# Differential_Opamp.net
KiCad netlist of a schematic drawn in Altium Designer
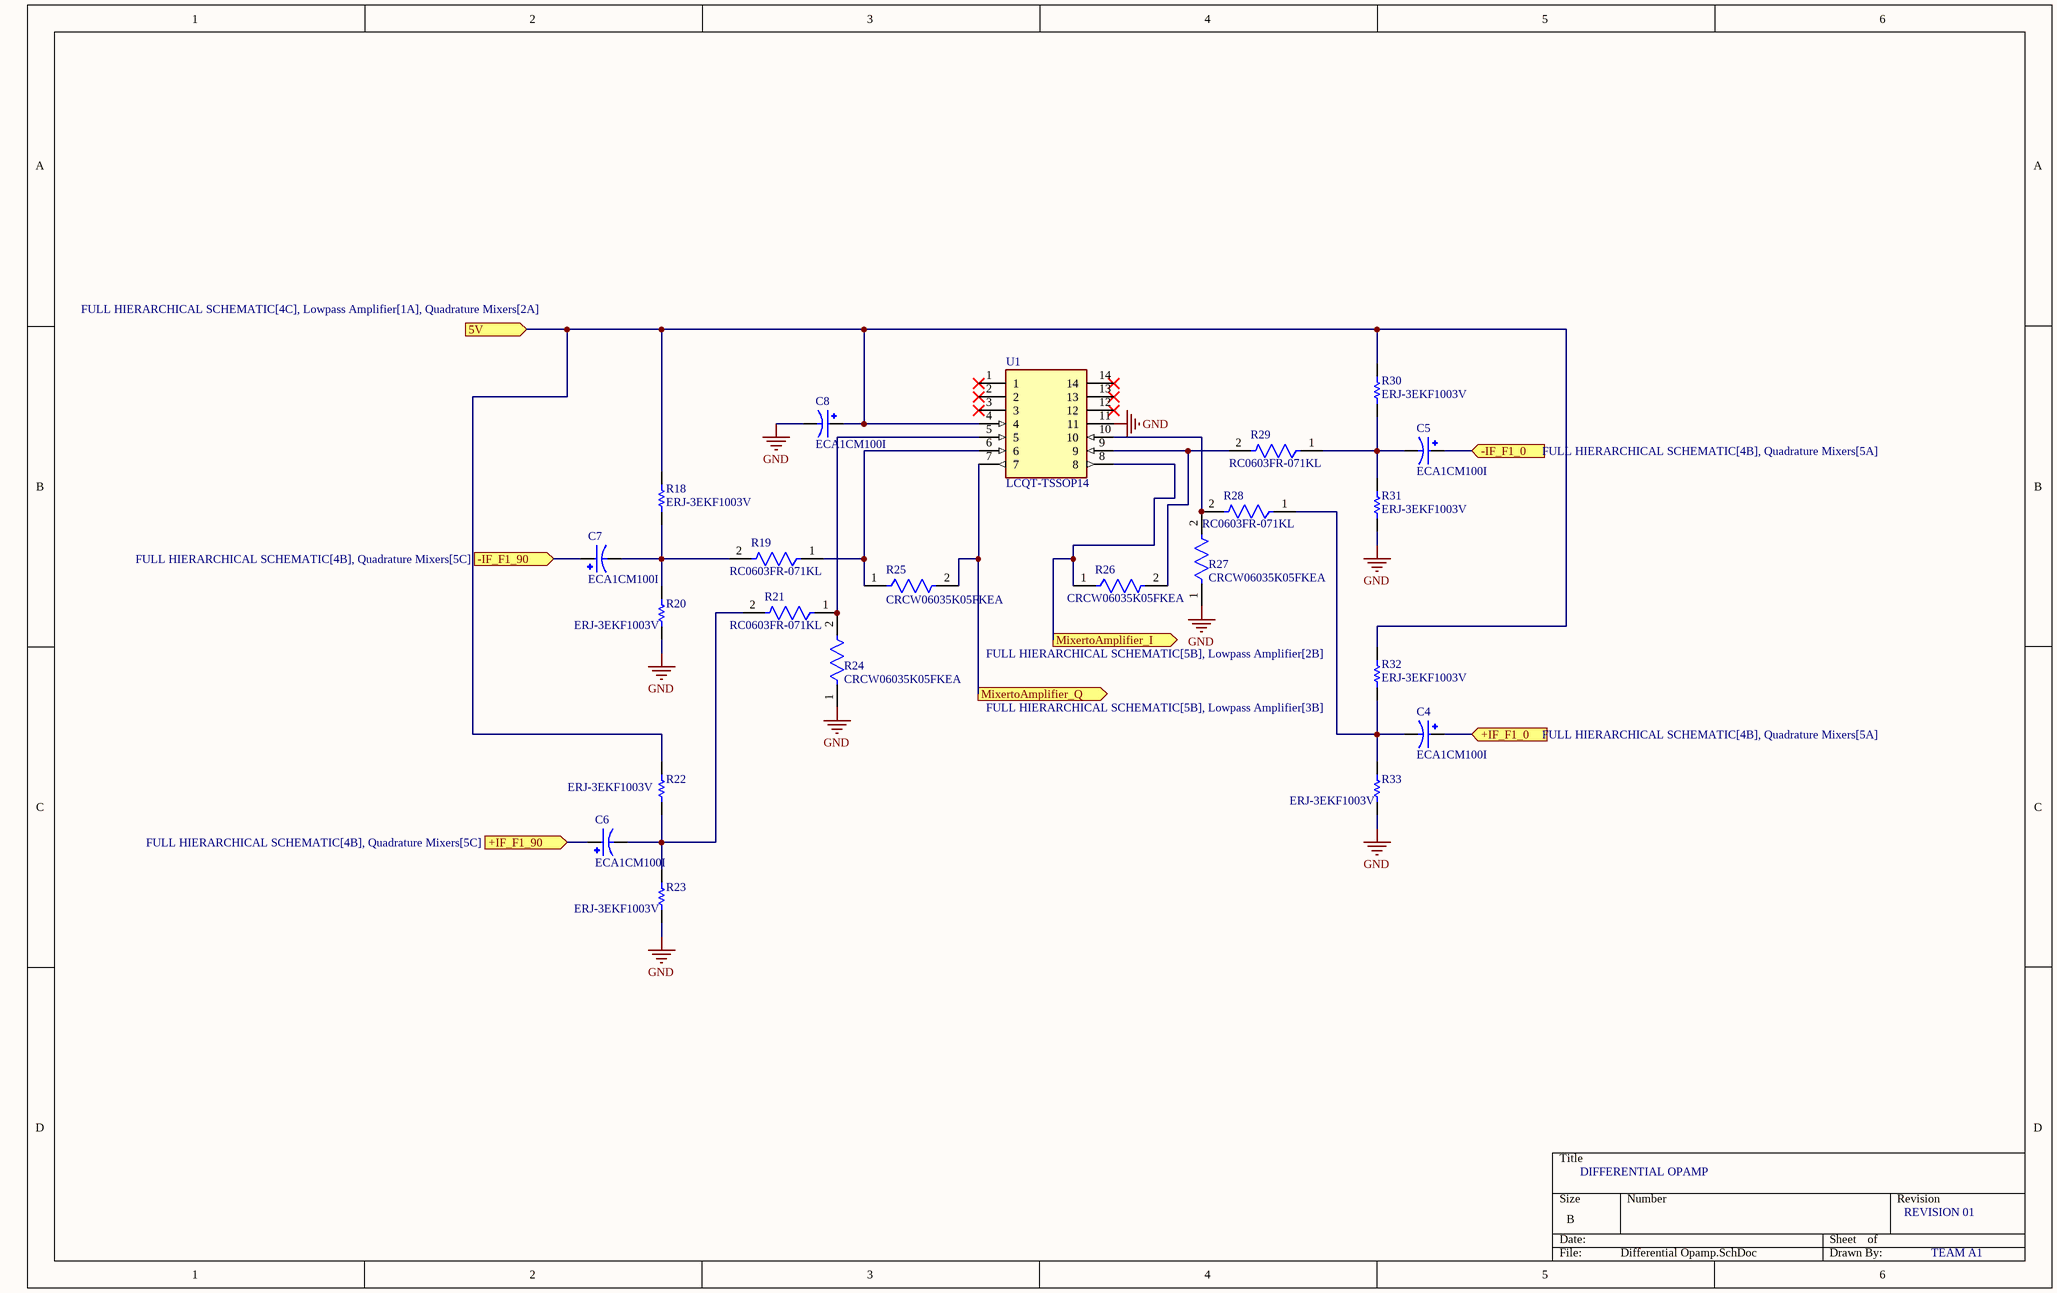
[diagram p0: Differential Opamp.SchDoc]

(export (version "E")
  (design (tool "Eeschema 10.0.6"))
  (components
    (comp (ref "C4")
      (value "ECA1CM100I")
      (footprint "CAPPRD250W50D500H1100")
      (description "10ÂµF 16V Aluminum Electrolytic Capacitors Radial, Can 2000 Hrs @ 85Â°C")
      (fields (field (name "DIGI-KEY_PART_NUMBER") "P19513TB-ND") (field (name "MF") "Panasonic"))
      (libsource (lib "ECA1CM100I") (part "ECA1CM100I"))
    )
    (comp (ref "C5")
      (value "ECA1CM100I")
      (footprint "CAPPRD250W50D500H1100")
      (description "10ÂµF 16V Aluminum Electrolytic Capacitors Radial, Can 2000 Hrs @ 85Â°C")
      (fields (field (name "DIGI-KEY_PART_NUMBER") "P19513TB-ND") (field (name "MF") "Panasonic"))
      (libsource (lib "ECA1CM100I") (part "ECA1CM100I"))
    )
    (comp (ref "C6")
      (value "ECA1CM100I")
      (footprint "CAPPRD250W50D500H1100")
      (description "10ÂµF 16V Aluminum Electrolytic Capacitors Radial, Can 2000 Hrs @ 85Â°C")
      (fields (field (name "DIGI-KEY_PART_NUMBER") "P19513TB-ND") (field (name "MF") "Panasonic"))
      (libsource (lib "") (part "ECA1CM100I_1"))
    )
    (comp (ref "C7")
      (value "ECA1CM100I")
      (footprint "CAPPRD250W50D500H1100")
      (description "10ÂµF 16V Aluminum Electrolytic Capacitors Radial, Can 2000 Hrs @ 85Â°C")
      (fields (field (name "DIGI-KEY_PART_NUMBER") "P19513TB-ND") (field (name "MF") "Panasonic"))
      (libsource (lib "") (part "ECA1CM100I_1"))
    )
    (comp (ref "C8")
      (value "ECA1CM100I")
      (footprint "CAPPRD250W50D500H1100")
      (description "10ÂµF 16V Aluminum Electrolytic Capacitors Radial, Can 2000 Hrs @ 85Â°C")
      (fields (field (name "DIGI-KEY_PART_NUMBER") "P19513TB-ND") (field (name "MF") "Panasonic"))
      (libsource (lib "ECA1CM100I") (part "ECA1CM100I"))
    )
    (comp (ref "R18")
      (value "ERJ-3EKF1003V")
      (footprint "RESC1608X55X30ML15T15")
      (fields (field (name "MANUFACTURER") "Panasonic"))
      (libsource (lib "Altium Content Vault") (part "RES"))
    )
    (comp (ref "R19")
      (value "RC0603FR-071KL")
      (footprint "FP-RC0603-0_55-IPC_C")
      (description "RES 1K OHM 1% 1/10W 0603")
      (fields (field (name "TOLERANCE") "1%"))
      (libsource (lib "Altium Content Vault") (part "1029c3af85768c4190bb7ad29bc67b5"))
    )
    (comp (ref "R20")
      (value "ERJ-3EKF1003V")
      (footprint "RESC1608X55X30ML15T15")
      (fields (field (name "MANUFACTURER") "Panasonic"))
      (libsource (lib "Altium Content Vault") (part "RES"))
    )
    (comp (ref "R21")
      (value "RC0603FR-071KL")
      (footprint "FP-RC0603-0_55-IPC_C")
      (description "RES 1K OHM 1% 1/10W 0603")
      (fields (field (name "TOLERANCE") "1%"))
      (libsource (lib "Altium Content Vault") (part "1029c3af85768c4190bb7ad29bc67b5"))
    )
    (comp (ref "R22")
      (value "ERJ-3EKF1003V")
      (footprint "RESC1608X55X30ML15T15")
      (fields (field (name "MANUFACTURER") "Panasonic"))
      (libsource (lib "Altium Content Vault") (part "RES"))
    )
    (comp (ref "R23")
      (value "ERJ-3EKF1003V")
      (footprint "RESC1608X55X30ML15T15")
      (fields (field (name "MANUFACTURER") "Panasonic"))
      (libsource (lib "Altium Content Vault") (part "RES"))
    )
    (comp (ref "R24")
      (value "CRCW06035K05FKEA")
      (footprint "FP-CRCW0603-e3-IPC_B")
      (description "RES Thick Film, 5.05kΩ, 1%, 0.1W, 100ppm/°C, 0603")
      (fields (field (name "TOLERANCE") "1%"))
      (libsource (lib "Altium Content Vault") (part "1029c3af85768c4190bb7ad29bc67b5"))
    )
    (comp (ref "R25")
      (value "CRCW06035K05FKEA")
      (footprint "FP-CRCW0603-e3-IPC_B")
      (description "RES Thick Film, 5.05kΩ, 1%, 0.1W, 100ppm/°C, 0603")
      (fields (field (name "TOLERANCE") "1%"))
      (libsource (lib "Altium Content Vault") (part "1029c3af85768c4190bb7ad29bc67b5"))
    )
    (comp (ref "R26")
      (value "CRCW06035K05FKEA")
      (footprint "FP-CRCW0603-e3-IPC_B")
      (description "RES Thick Film, 5.05kΩ, 1%, 0.1W, 100ppm/°C, 0603")
      (fields (field (name "TOLERANCE") "1%"))
      (libsource (lib "Altium Content Vault") (part "1029c3af85768c4190bb7ad29bc67b5"))
    )
    (comp (ref "R27")
      (value "CRCW06035K05FKEA")
      (footprint "FP-CRCW0603-e3-IPC_B")
      (description "RES Thick Film, 5.05kΩ, 1%, 0.1W, 100ppm/°C, 0603")
      (fields (field (name "TOLERANCE") "1%"))
      (libsource (lib "Altium Content Vault") (part "1029c3af85768c4190bb7ad29bc67b5"))
    )
    (comp (ref "R28")
      (value "RC0603FR-071KL")
      (footprint "FP-RC0603-0_55-IPC_C")
      (description "RES 1K OHM 1% 1/10W 0603")
      (fields (field (name "TOLERANCE") "1%"))
      (libsource (lib "Altium Content Vault") (part "1029c3af85768c4190bb7ad29bc67b5"))
    )
    (comp (ref "R29")
      (value "RC0603FR-071KL")
      (footprint "FP-RC0603-0_55-IPC_C")
      (description "RES 1K OHM 1% 1/10W 0603")
      (fields (field (name "TOLERANCE") "1%"))
      (libsource (lib "Altium Content Vault") (part "1029c3af85768c4190bb7ad29bc67b5"))
    )
    (comp (ref "R30")
      (value "ERJ-3EKF1003V")
      (footprint "RESC1608X55X30ML15T15")
      (fields (field (name "MANUFACTURER") "Panasonic"))
      (libsource (lib "Altium Content Vault") (part "RES"))
    )
    (comp (ref "R31")
      (value "ERJ-3EKF1003V")
      (footprint "RESC1608X55X30ML15T15")
      (fields (field (name "MANUFACTURER") "Panasonic"))
      (libsource (lib "Altium Content Vault") (part "RES"))
    )
    (comp (ref "R32")
      (value "ERJ-3EKF1003V")
      (footprint "RESC1608X55X30ML15T15")
      (fields (field (name "MANUFACTURER") "Panasonic"))
      (libsource (lib "Altium Content Vault") (part "RES"))
    )
    (comp (ref "R33")
      (value "ERJ-3EKF1003V")
      (footprint "RESC1608X55X30ML15T15")
      (fields (field (name "MANUFACTURER") "Panasonic"))
      (libsource (lib "Altium Content Vault") (part "RES"))
    )
    (comp (ref "U1")
      (value "LCQT-TSSOP14")
      (footprint "ARIES_LCQT-TSSOP14")
      (description "SOCKET ADAPTER TSSOP TO 14DIP")
      (fields (field (name "MF") "Aries Electronics"))
      (libsource (lib "LCQT-TSSOP14") (part "LCQT-TSSOP14"))
    )
  )
  (nets
    (net (code "1") (name "/+IF_F1_0") (class "Default")
      (node (ref "C4") (pin "P") (pinfunction "P_P") (pintype "passive"))
    )
    (net (code "2") (name "/+IF_F1_90") (class "Default")
      (node (ref "C6") (pin "P") (pinfunction "P_P") (pintype "passive"))
    )
    (net (code "3") (name "/-IF_F1_0") (class "Default")
      (node (ref "C5") (pin "P") (pinfunction "P_P") (pintype "passive"))
    )
    (net (code "4") (name "/-IF_F1_90") (class "Default")
      (node (ref "C7") (pin "P") (pinfunction "P_P") (pintype "passive"))
    )
    (net (code "5") (name "/5V") (class "Default")
      (node (ref "C8") (pin "P") (pinfunction "P_P") (pintype "passive"))
      (node (ref "R18") (pin "2") (pinfunction "2_2") (pintype "passive"))
      (node (ref "R22") (pin "2") (pinfunction "2_2") (pintype "passive"))
      (node (ref "R30") (pin "2") (pinfunction "2_2") (pintype "passive"))
      (node (ref "R32") (pin "2") (pinfunction "2_2") (pintype "passive"))
      (node (ref "U1") (pin "4") (pinfunction "4_4") (pintype "input"))
    )
    (net (code "6") (name "/MixertoAmplifier_I") (class "Default")
      (node (ref "R26") (pin "1") (pinfunction "1_1") (pintype "passive"))
      (node (ref "U1") (pin "8") (pinfunction "8_8") (pintype "output"))
    )
    (net (code "7") (name "/MixertoAmplifier_Q") (class "Default")
      (node (ref "R25") (pin "2") (pinfunction "2_2") (pintype "passive"))
      (node (ref "U1") (pin "7") (pinfunction "7_7") (pintype "output"))
    )
    (net (code "8") (name "GND") (class "Default")
      (node (ref "C8") (pin "N") (pinfunction "N_N") (pintype "passive"))
      (node (ref "R20") (pin "1") (pinfunction "1_1") (pintype "passive"))
      (node (ref "R23") (pin "1") (pinfunction "1_1") (pintype "passive"))
      (node (ref "R24") (pin "1") (pinfunction "1_1") (pintype "passive"))
      (node (ref "R27") (pin "1") (pinfunction "1_1") (pintype "passive"))
      (node (ref "R31") (pin "1") (pinfunction "1_1") (pintype "passive"))
      (node (ref "R33") (pin "1") (pinfunction "1_1") (pintype "passive"))
      (node (ref "U1") (pin "11") (pinfunction "11_11") (pintype "passive"))
    )
    (net (code "9") (name "Net-(C4-PadN)") (class "Default")
      (node (ref "C4") (pin "N") (pinfunction "N_N") (pintype "passive"))
      (node (ref "R28") (pin "1") (pinfunction "1_1") (pintype "passive"))
      (node (ref "R32") (pin "1") (pinfunction "1_1") (pintype "passive"))
      (node (ref "R33") (pin "2") (pinfunction "2_2") (pintype "passive"))
    )
    (net (code "10") (name "Net-(C5-PadN)") (class "Default")
      (node (ref "C5") (pin "N") (pinfunction "N_N") (pintype "passive"))
      (node (ref "R29") (pin "1") (pinfunction "1_1") (pintype "passive"))
      (node (ref "R30") (pin "1") (pinfunction "1_1") (pintype "passive"))
      (node (ref "R31") (pin "2") (pinfunction "2_2") (pintype "passive"))
    )
    (net (code "11") (name "Net-(C6-PadN)") (class "Default")
      (node (ref "C6") (pin "N") (pinfunction "N_N") (pintype "passive"))
      (node (ref "R21") (pin "2") (pinfunction "2_2") (pintype "passive"))
      (node (ref "R22") (pin "1") (pinfunction "1_1") (pintype "passive"))
      (node (ref "R23") (pin "2") (pinfunction "2_2") (pintype "passive"))
    )
    (net (code "12") (name "Net-(C7-PadN)") (class "Default")
      (node (ref "C7") (pin "N") (pinfunction "N_N") (pintype "passive"))
      (node (ref "R18") (pin "1") (pinfunction "1_1") (pintype "passive"))
      (node (ref "R19") (pin "2") (pinfunction "2_2") (pintype "passive"))
      (node (ref "R20") (pin "2") (pinfunction "2_2") (pintype "passive"))
    )
    (net (code "13") (name "Net-(R19-Pad1)") (class "Default")
      (node (ref "R19") (pin "1") (pinfunction "1_1") (pintype "passive"))
      (node (ref "R25") (pin "1") (pinfunction "1_1") (pintype "passive"))
      (node (ref "U1") (pin "6") (pinfunction "6_6") (pintype "input"))
    )
    (net (code "14") (name "Net-(R21-Pad1)") (class "Default")
      (node (ref "R21") (pin "1") (pinfunction "1_1") (pintype "passive"))
      (node (ref "R24") (pin "2") (pinfunction "2_2") (pintype "passive"))
      (node (ref "U1") (pin "5") (pinfunction "5_5") (pintype "input"))
    )
    (net (code "15") (name "Net-(R26-Pad2)") (class "Default")
      (node (ref "R26") (pin "2") (pinfunction "2_2") (pintype "passive"))
      (node (ref "R29") (pin "2") (pinfunction "2_2") (pintype "passive"))
      (node (ref "U1") (pin "9") (pinfunction "9_9") (pintype "input"))
    )
    (net (code "16") (name "Net-(R27-Pad2)") (class "Default")
      (node (ref "R27") (pin "2") (pinfunction "2_2") (pintype "passive"))
      (node (ref "R28") (pin "2") (pinfunction "2_2") (pintype "passive"))
      (node (ref "U1") (pin "10") (pinfunction "10_10") (pintype "input"))
    )
    (net (code "17") (name "unconnected-(U1-Pad1)") (class "Default")
      (node (ref "U1") (pin "1") (pinfunction "1_1") (pintype "passive+no_connect"))
    )
    (net (code "18") (name "unconnected-(U1-Pad2)") (class "Default")
      (node (ref "U1") (pin "2") (pinfunction "2_2") (pintype "passive+no_connect"))
    )
    (net (code "19") (name "unconnected-(U1-Pad3)") (class "Default")
      (node (ref "U1") (pin "3") (pinfunction "3_3") (pintype "passive+no_connect"))
    )
    (net (code "20") (name "unconnected-(U1-Pad12)") (class "Default")
      (node (ref "U1") (pin "12") (pinfunction "12_12") (pintype "passive+no_connect"))
    )
    (net (code "21") (name "unconnected-(U1-Pad13)") (class "Default")
      (node (ref "U1") (pin "13") (pinfunction "13_13") (pintype "passive+no_connect"))
    )
    (net (code "22") (name "unconnected-(U1-Pad14)") (class "Default")
      (node (ref "U1") (pin "14") (pinfunction "14_14") (pintype "passive+no_connect"))
    )
  )
)
